# jtag.net
KiCad netlist of a schematic drawn in Altium Designer
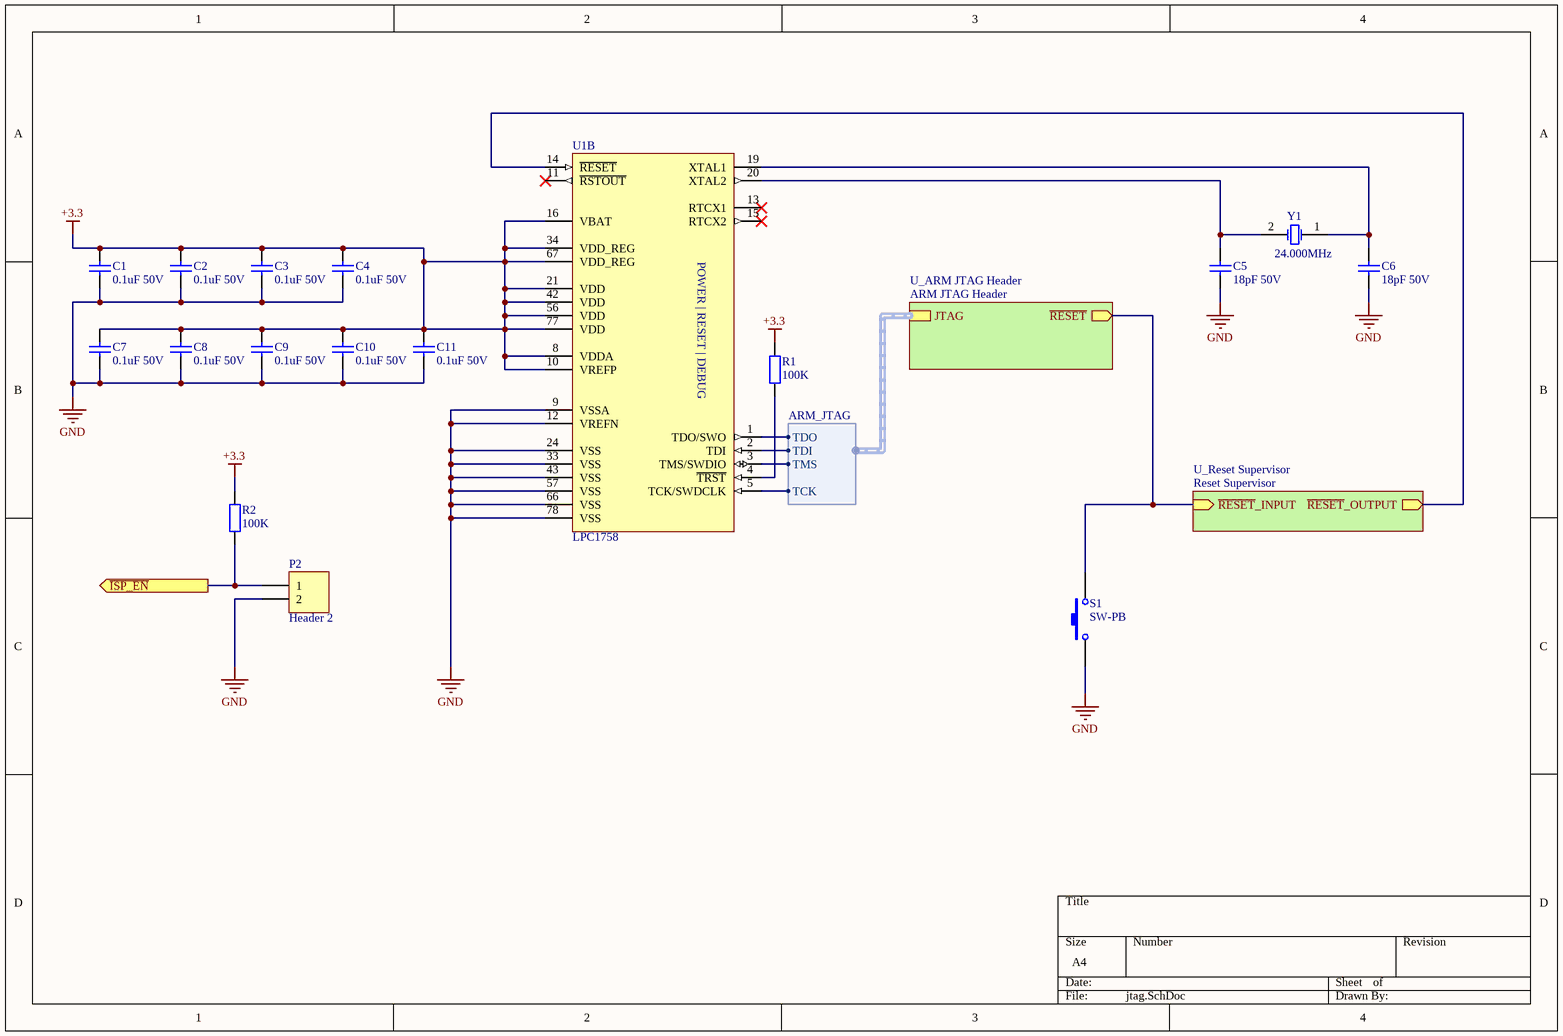
[diagram p0: jtag.SchDoc]

(export (version "E")
  (design (tool "Eeschema 10.0.6"))
  (components
    (comp (ref "C1")
      (value "0.1uF 50V")
      (footprint "C0805")
      (description "Capacitor")
      (fields (field (name "Comment") "Cap"))
      (libsource (lib "Miscellaneous Devices") (part "Cap"))
    )
    (comp (ref "C2")
      (value "0.1uF 50V")
      (footprint "C0805")
      (description "Capacitor")
      (fields (field (name "Comment") "Cap"))
      (libsource (lib "Miscellaneous Devices") (part "Cap"))
    )
    (comp (ref "C3")
      (value "0.1uF 50V")
      (footprint "C0805")
      (description "Capacitor")
      (fields (field (name "Comment") "Cap"))
      (libsource (lib "Miscellaneous Devices") (part "Cap"))
    )
    (comp (ref "C4")
      (value "0.1uF 50V")
      (footprint "C0805")
      (description "Capacitor")
      (fields (field (name "Comment") "Cap"))
      (libsource (lib "Miscellaneous Devices") (part "Cap"))
    )
    (comp (ref "C5")
      (value "18pF 50V")
      (footprint "C0805")
      (description "Capacitor")
      (fields (field (name "Comment") "Cap"))
      (libsource (lib "Miscellaneous Devices") (part "Cap"))
    )
    (comp (ref "C6")
      (value "18pF 50V")
      (footprint "C0805")
      (description "Capacitor")
      (fields (field (name "Comment") "Cap"))
      (libsource (lib "Miscellaneous Devices") (part "Cap"))
    )
    (comp (ref "C7")
      (value "0.1uF 50V")
      (footprint "C0805")
      (description "Capacitor")
      (fields (field (name "Comment") "Cap"))
      (libsource (lib "Miscellaneous Devices") (part "Cap"))
    )
    (comp (ref "C8")
      (value "0.1uF 50V")
      (footprint "C0805")
      (description "Capacitor")
      (fields (field (name "Comment") "Cap"))
      (libsource (lib "Miscellaneous Devices") (part "Cap"))
    )
    (comp (ref "C9")
      (value "0.1uF 50V")
      (footprint "C0805")
      (description "Capacitor")
      (fields (field (name "Comment") "Cap"))
      (libsource (lib "Miscellaneous Devices") (part "Cap"))
    )
    (comp (ref "C10")
      (value "0.1uF 50V")
      (footprint "C0805")
      (description "Capacitor")
      (fields (field (name "Comment") "Cap"))
      (libsource (lib "Miscellaneous Devices") (part "Cap"))
    )
    (comp (ref "C11")
      (value "0.1uF 50V")
      (footprint "C0805")
      (description "Capacitor")
      (fields (field (name "Comment") "Cap"))
      (libsource (lib "Miscellaneous Devices") (part "Cap"))
    )
    (comp (ref "P2")
      (value "Header 2")
      (footprint "HDR1X2")
      (description "Header, 2-Pin")
      (fields (field (name "PUBLISHER") "Altium Limited"))
      (libsource (lib "Miscellaneous Connectors") (part "Header 2"))
    )
    (comp (ref "R1")
      (value "100K")
      (footprint "R0603")
      (description "Resistor")
      (fields (field (name "Comment") "Res"))
      (libsource (lib "Miscellaneous Devices") (part "Res2"))
    )
    (comp (ref "R2")
      (value "100K")
      (footprint "R0603")
      (description "Resistor")
      (fields (field (name "Comment") "Res"))
      (libsource (lib "Miscellaneous Devices") (part "Res2"))
    )
    (comp (ref "S1")
      (value "SW-PB")
      (footprint "DTSM-32S-B")
      (description "Switch")
      (fields (field (name "PUBLISHER") "Altium Limited"))
      (libsource (lib "Miscellaneous Devices") (part "SW-PB"))
    )
    (comp (ref "U1")
      (value "LPC1758")
      (footprint "LPC1758FBD80")
      (description "NXP - LPC1758FBD80 - MCU, 32BIT, ARM CORTEX M3, 80LQFP")
      (libsource (lib "LPC1758") (part "LPC1758"))
    )
    (comp (ref "Y1")
      (value "24.000MHz")
      (footprint "C3E-24.000-12-3030-X")
      (description "Crystal Oscillator")
      (fields (field (name "Comment") "XTAL"))
      (libsource (lib "Miscellaneous Devices") (part "XTAL"))
    )
  )
  (nets
    (net (code "2") (name "+3.3") (class "Default")
      (node (ref "C1") (pin "1") (pinfunction "1_1") (pintype "passive"))
      (node (ref "C10") (pin "1") (pinfunction "1_1") (pintype "passive"))
      (node (ref "C11") (pin "1") (pinfunction "1_1") (pintype "passive"))
      (node (ref "C2") (pin "1") (pinfunction "1_1") (pintype "passive"))
      (node (ref "C3") (pin "1") (pinfunction "1_1") (pintype "passive"))
      (node (ref "C4") (pin "1") (pinfunction "1_1") (pintype "passive"))
      (node (ref "C7") (pin "1") (pinfunction "1_1") (pintype "passive"))
      (node (ref "C8") (pin "1") (pinfunction "1_1") (pintype "passive"))
      (node (ref "C9") (pin "1") (pinfunction "1_1") (pintype "passive"))
      (node (ref "R1") (pin "2") (pinfunction "2_2") (pintype "passive"))
      (node (ref "R2") (pin "2") (pinfunction "2_2") (pintype "passive"))
      (node (ref "U1") (pin "10") (pinfunction "VREFP_10") (pintype "passive"))
      (node (ref "U1") (pin "16") (pinfunction "VBAT_16") (pintype "power_in"))
      (node (ref "U1") (pin "21") (pinfunction "VDD_21") (pintype "power_in"))
      (node (ref "U1") (pin "34") (pinfunction "VDD_REG_34") (pintype "power_in"))
      (node (ref "U1") (pin "42") (pinfunction "VDD_42") (pintype "power_in"))
      (node (ref "U1") (pin "56") (pinfunction "VDD_56") (pintype "power_in"))
      (node (ref "U1") (pin "67") (pinfunction "VDD_REG_67") (pintype "power_in"))
      (node (ref "U1") (pin "77") (pinfunction "VDD_77") (pintype "power_in"))
      (node (ref "U1") (pin "8") (pinfunction "VDDA_8") (pintype "power_in"))
    )
    (net (code "3") (name "/TCK") (class "Default")
      (node (ref "U1") (pin "5") (pinfunction "TCK/SWDCLK_5") (pintype "input"))
    )
    (net (code "4") (name "/TDI") (class "Default")
      (node (ref "U1") (pin "2") (pinfunction "TDI_2") (pintype "input"))
    )
    (net (code "5") (name "/TDO") (class "Default")
      (node (ref "U1") (pin "1") (pinfunction "TDO/SWO_1") (pintype "output"))
    )
    (net (code "6") (name "/TMS") (class "Default")
      (node (ref "U1") (pin "3") (pinfunction "TMS/SWDIO_3") (pintype "bidirectional"))
    )
    (net (code "8") (name "/~{ISP_EN}") (class "Default")
      (node (ref "P2") (pin "1") (pinfunction "1_1") (pintype "passive"))
      (node (ref "R2") (pin "1") (pinfunction "1_1") (pintype "passive"))
    )
    (net (code "9") (name "/~{RESET}") (class "Default")
      (node (ref "S1") (pin "2") (pinfunction "2_2") (pintype "passive"))
    )
    (net (code "10") (name "/~{RESET}_OUTPUT") (class "Default")
      (node (ref "U1") (pin "14") (pinfunction "~{RESET}_14") (pintype "input"))
    )
    (net (code "11") (name "GND") (class "Default")
      (node (ref "C1") (pin "2") (pinfunction "2_2") (pintype "passive"))
      (node (ref "C10") (pin "2") (pinfunction "2_2") (pintype "passive"))
      (node (ref "C11") (pin "2") (pinfunction "2_2") (pintype "passive"))
      (node (ref "C2") (pin "2") (pinfunction "2_2") (pintype "passive"))
      (node (ref "C3") (pin "2") (pinfunction "2_2") (pintype "passive"))
      (node (ref "C4") (pin "2") (pinfunction "2_2") (pintype "passive"))
      (node (ref "C5") (pin "2") (pinfunction "2_2") (pintype "passive"))
      (node (ref "C6") (pin "2") (pinfunction "2_2") (pintype "passive"))
      (node (ref "C7") (pin "2") (pinfunction "2_2") (pintype "passive"))
      (node (ref "C8") (pin "2") (pinfunction "2_2") (pintype "passive"))
      (node (ref "C9") (pin "2") (pinfunction "2_2") (pintype "passive"))
      (node (ref "P2") (pin "2") (pinfunction "2_2") (pintype "passive"))
      (node (ref "S1") (pin "1") (pinfunction "1_1") (pintype "passive"))
      (node (ref "U1") (pin "12") (pinfunction "VREFN_12") (pintype "passive"))
      (node (ref "U1") (pin "24") (pinfunction "VSS_24") (pintype "power_in"))
      (node (ref "U1") (pin "33") (pinfunction "VSS_33") (pintype "power_in"))
      (node (ref "U1") (pin "43") (pinfunction "VSS_43") (pintype "power_in"))
      (node (ref "U1") (pin "57") (pinfunction "VSS_57") (pintype "power_in"))
      (node (ref "U1") (pin "66") (pinfunction "VSS_66") (pintype "power_in"))
      (node (ref "U1") (pin "78") (pinfunction "VSS_78") (pintype "power_in"))
      (node (ref "U1") (pin "9") (pinfunction "VSSA_9") (pintype "power_in"))
    )
    (net (code "12") (name "Net-(U1B-XTAL1)") (class "Default")
      (node (ref "C6") (pin "1") (pinfunction "1_1") (pintype "passive"))
      (node (ref "U1") (pin "19") (pinfunction "XTAL1_19") (pintype "passive"))
      (node (ref "Y1") (pin "1") (pinfunction "OSC1_1") (pintype "passive"))
    )
    (net (code "13") (name "Net-(U1B-XTAL2)") (class "Default")
      (node (ref "C5") (pin "1") (pinfunction "1_1") (pintype "passive"))
      (node (ref "U1") (pin "20") (pinfunction "XTAL2_20") (pintype "output"))
      (node (ref "Y1") (pin "2") (pinfunction "OSC2_2") (pintype "passive"))
    )
    (net (code "14") (name "Net-(U1B-~{TRST})") (class "Default")
      (node (ref "R1") (pin "1") (pinfunction "1_1") (pintype "passive"))
      (node (ref "U1") (pin "4") (pinfunction "~{TRST}_4") (pintype "input"))
    )
    (net (code "15") (name "unconnected-(U1B-RTCX1-Pad13)") (class "Default")
      (node (ref "U1") (pin "13") (pinfunction "RTCX1_13") (pintype "passive+no_connect"))
    )
    (net (code "16") (name "unconnected-(U1B-RTCX2-Pad15)") (class "Default")
      (node (ref "U1") (pin "15") (pinfunction "RTCX2_15") (pintype "output+no_connect"))
    )
    (net (code "17") (name "unconnected-(U1B-~{RSTOUT}-Pad11)") (class "Default")
      (node (ref "U1") (pin "11") (pinfunction "~{RSTOUT}_11") (pintype "output+no_connect"))
    )
  )
)
